# bat-phone_Dodo.net
KiCad netlist of a schematic drawn in EAGLE
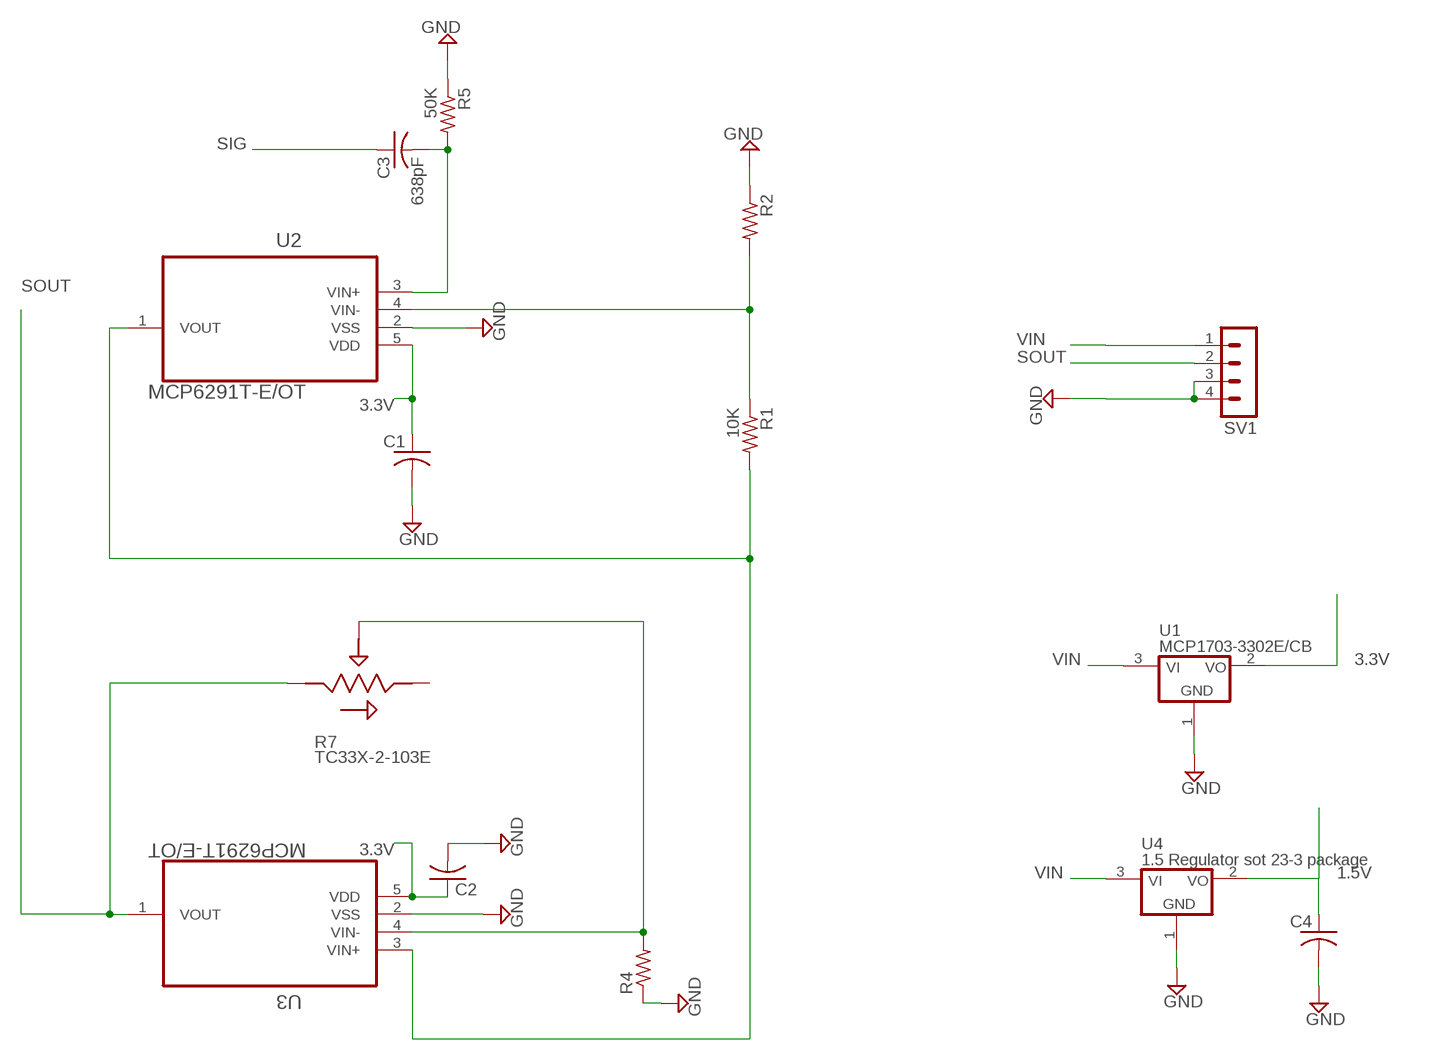
[diagram p0: schematic, sheet 1]

(export (version "E")
  (design (tool "Eeschema 10.0.6"))
  (components
    (comp (ref "C1")
      (value "C-USC0603K")
      (footprint "eagle-import:C0603K")
      (libsource (lib "eagle-import") (part "C-USC0603K"))
    )
    (comp (ref "C2")
      (value "C-USC0603K")
      (footprint "eagle-import:C0603K")
      (libsource (lib "eagle-import") (part "C-USC0603K"))
    )
    (comp (ref "C3")
      (value "638pF")
      (footprint "eagle-import:C0603K")
      (libsource (lib "eagle-import") (part "C-USC0603K"))
    )
    (comp (ref "C4")
      (value "C-USC0603K")
      (footprint "eagle-import:C0603K")
      (libsource (lib "eagle-import") (part "C-USC0603K"))
    )
    (comp (ref "R1")
      (value "10K")
      (footprint "eagle-import:R0603")
      (libsource (lib "eagle-import") (part "R-US_R0603"))
    )
    (comp (ref "R2")
      (value "R-US_R0603")
      (footprint "eagle-import:R0603")
      (libsource (lib "eagle-import") (part "R-US_R0603"))
    )
    (comp (ref "R4")
      (value "R-US_R0603")
      (footprint "eagle-import:R0603")
      (libsource (lib "eagle-import") (part "R-US_R0603"))
    )
    (comp (ref "R5")
      (value "50K")
      (footprint "eagle-import:R0603")
      (libsource (lib "eagle-import") (part "R-US_R0603"))
    )
    (comp (ref "R7")
      (value "TC33X-2-103E")
      (footprint "eagle-import:35WR")
      (fields (field (name "MF") "Bourns"))
      (libsource (lib "eagle-import") (part "TC33X-2-103E"))
    )
    (comp (ref "SV1")
      (value "MA04-1")
      (footprint "eagle-import:MA04-1")
      (libsource (lib "eagle-import") (part "MA04-1"))
    )
    (comp (ref "U1")
      (value "MCP1703-3302E/CB")
      (footprint "eagle-import:SOT23A_MICROCHIP_CB")
      (libsource (lib "eagle-import") (part "MCP170302E/CB-33"))
    )
    (comp (ref "U2")
      (value "MCP6291T-E/OT")
      (footprint "eagle-import:SOT95P320X145-5N")
      (fields (field (name "MF") "Microchip"))
      (libsource (lib "eagle-import") (part "MCP6291T-E/OT"))
    )
    (comp (ref "U3")
      (value "MCP6291T-E/OT")
      (footprint "eagle-import:SOT95P320X145-5N")
      (fields (field (name "MF") "Microchip"))
      (libsource (lib "eagle-import") (part "MCP6291T-E/OT"))
    )
    (comp (ref "U4")
      (value "1.5 Regulator sot 23-3 package")
      (footprint "eagle-import:SOT23A_MICROCHIP_CB")
      (libsource (lib "eagle-import") (part "MCP170302E/CB-33"))
    )
  )
  (nets
    (net (code "1") (name "/1.5V") (class "Default")
      (node (ref "C4") (pin "1") (pinfunction "1_1") (pintype "passive"))
      (node (ref "U4") (pin "2") (pinfunction "VO_2") (pintype "passive"))
    )
    (net (code "2") (name "/3.3V") (class "Default")
      (node (ref "C1") (pin "1") (pinfunction "1_1") (pintype "passive"))
      (node (ref "C2") (pin "1") (pinfunction "1_1") (pintype "passive"))
      (node (ref "U1") (pin "2") (pinfunction "VO_2") (pintype "passive"))
      (node (ref "U2") (pin "5") (pinfunction "VDD_5") (pintype "power_in"))
      (node (ref "U3") (pin "5") (pinfunction "VDD_5") (pintype "power_in"))
    )
    (net (code "3") (name "/SIG") (class "Default")
      (node (ref "C3") (pin "1") (pinfunction "1_1") (pintype "passive"))
    )
    (net (code "4") (name "/SOUT") (class "Default")
      (node (ref "R7") (pin "1") (pinfunction "1_1") (pintype "passive"))
      (node (ref "SV1") (pin "2") (pinfunction "2_2") (pintype "passive"))
      (node (ref "U3") (pin "1") (pinfunction "VOUT_1") (pintype "output"))
    )
    (net (code "5") (name "/VIN") (class "Default")
      (node (ref "SV1") (pin "1") (pinfunction "1_1") (pintype "passive"))
      (node (ref "U1") (pin "3") (pinfunction "VI_3") (pintype "power_in"))
      (node (ref "U4") (pin "3") (pinfunction "VI_3") (pintype "power_in"))
    )
    (net (code "6") (name "GND") (class "Default")
      (node (ref "C1") (pin "2") (pinfunction "2_2") (pintype "passive"))
      (node (ref "C2") (pin "2") (pinfunction "2_2") (pintype "passive"))
      (node (ref "C4") (pin "2") (pinfunction "2_2") (pintype "passive"))
      (node (ref "R2") (pin "1") (pinfunction "1_1") (pintype "passive"))
      (node (ref "R4") (pin "1") (pinfunction "1_1") (pintype "passive"))
      (node (ref "R5") (pin "1") (pinfunction "1_1") (pintype "passive"))
      (node (ref "SV1") (pin "3") (pinfunction "3_3") (pintype "passive"))
      (node (ref "SV1") (pin "4") (pinfunction "4_4") (pintype "passive"))
      (node (ref "U1") (pin "1") (pinfunction "GND_1") (pintype "power_in"))
      (node (ref "U2") (pin "2") (pinfunction "VSS_2") (pintype "passive"))
      (node (ref "U3") (pin "2") (pinfunction "VSS_2") (pintype "passive"))
      (node (ref "U4") (pin "1") (pinfunction "GND_1") (pintype "power_in"))
    )
    (net (code "7") (name "Net-(U2-VIN+)") (class "Default")
      (node (ref "C3") (pin "2") (pinfunction "2_2") (pintype "passive"))
      (node (ref "R5") (pin "2") (pinfunction "2_2") (pintype "passive"))
      (node (ref "U2") (pin "3") (pinfunction "VIN+_3") (pintype "input"))
    )
    (net (code "8") (name "Net-(U2-VIN-)") (class "Default")
      (node (ref "R1") (pin "1") (pinfunction "1_1") (pintype "passive"))
      (node (ref "R2") (pin "2") (pinfunction "2_2") (pintype "passive"))
      (node (ref "U2") (pin "4") (pinfunction "VIN-_4") (pintype "input"))
    )
    (net (code "9") (name "Net-(U2-VOUT)") (class "Default")
      (node (ref "R1") (pin "2") (pinfunction "2_2") (pintype "passive"))
      (node (ref "U2") (pin "1") (pinfunction "VOUT_1") (pintype "output"))
      (node (ref "U3") (pin "3") (pinfunction "VIN+_3") (pintype "input"))
    )
    (net (code "10") (name "Net-(U3-VIN-)") (class "Default")
      (node (ref "R4") (pin "2") (pinfunction "2_2") (pintype "passive"))
      (node (ref "R7") (pin "2") (pinfunction "2_2") (pintype "passive"))
      (node (ref "U3") (pin "4") (pinfunction "VIN-_4") (pintype "input"))
    )
    (net (code "11") (name "unconnected-(R7-Pad3)") (class "Default")
      (node (ref "R7") (pin "3") (pinfunction "3_3") (pintype "passive"))
    )
  )
)
